# 190822_Top_Level.net
KiCad netlist of a schematic drawn in Altium Designer
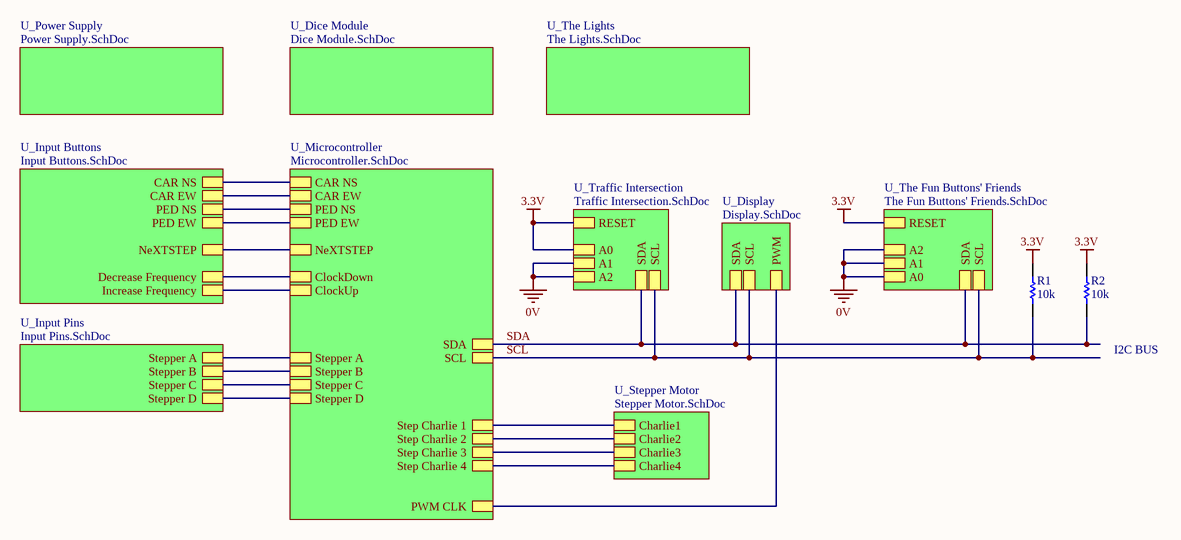
[diagram p0: 190822 Top Level.SchDoc]

(export (version "E")
  (design (tool "Eeschema 10.0.6"))
  (components
    (comp (ref "R1")
      (value "10k")
      (footprint "0805")
      (fields
        (field (name "PART NUMBER") "RC0805FR0710KL")
        (field (name "MANUFACTURER") "YAGEO")
        (field (name "TOLERANCE") "0.01")
      )
      (libsource (lib "ts_19-standard-library-IED") (part "Resistor"))
    )
    (comp (ref "R2")
      (value "10k")
      (footprint "0805")
      (fields
        (field (name "PART NUMBER") "RC0805FR0710KL")
        (field (name "MANUFACTURER") "YAGEO")
        (field (name "TOLERANCE") "0.01")
      )
      (libsource (lib "ts_19-standard-library-IED") (part "Resistor"))
    )
  )
  (nets
    (net (code "13") (name "/SCL") (class "Default")
      (node (ref "R1") (pin "2") (pinfunction "2_2") (pintype "passive"))
    )
    (net (code "14") (name "/SDA") (class "Default")
      (node (ref "R2") (pin "2") (pinfunction "2_2") (pintype "passive"))
    )
    (net (code "20") (name "3.3V") (class "Default")
      (node (ref "R1") (pin "1") (pinfunction "1_1") (pintype "passive"))
      (node (ref "R2") (pin "1") (pinfunction "1_1") (pintype "passive"))
    )
  )
)
